# ADS1299IPAG.net
KiCad netlist of a schematic drawn in Altium Designer
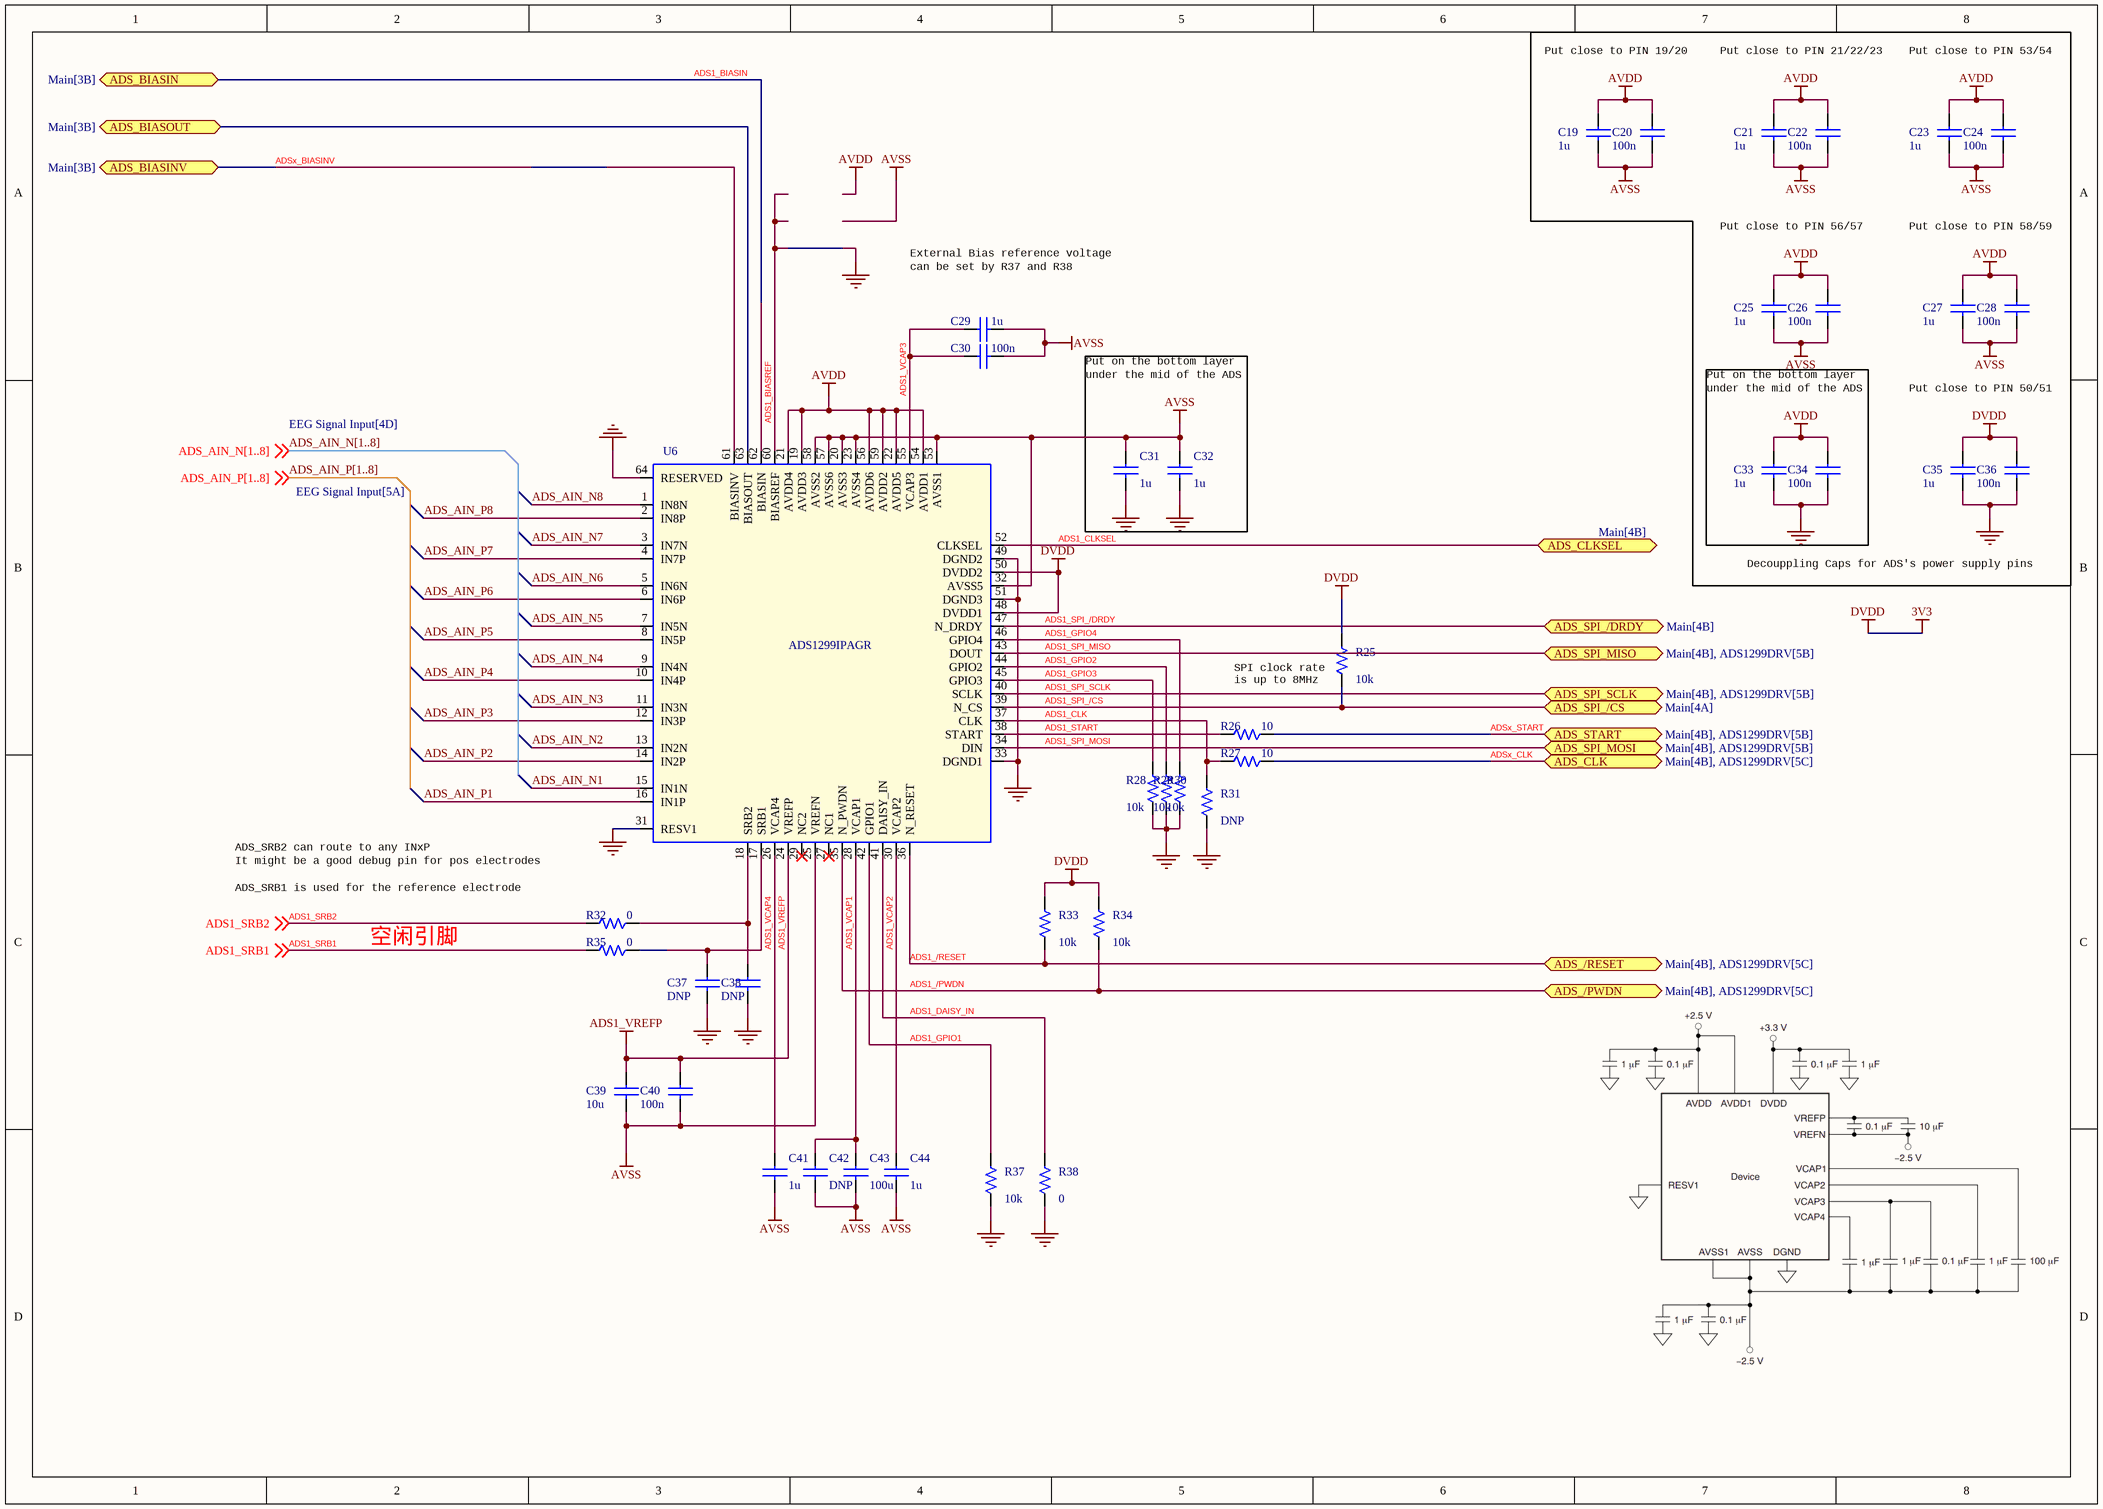
[diagram p0: ADS1299IPAG.SchDoc]

(export (version "E")
  (design (tool "Eeschema 10.0.6"))
  (components
    (comp (ref "C19")
      (value "1u")
      (footprint "0201_C")
      (description "CAP CER 1UF 25V X5R 0402")
      (fields
        (field (name "DISTRIBUTOR PART NUMBER") "C326568")
        (field (name "PART NUMBER") "CC0402KRX5R8BB105")
      )
      (libsource (lib "*") (part "CAP0402"))
    )
    (comp (ref "C20")
      (value "100n")
      (footprint "0201_C")
      (description "CAP CER 0.1UF 25V X7R 0402")
      (fields
        (field (name "DISTRIBUTOR PART NUMBER") "C105883")
        (field (name "PART NUMBER") "CC0402KRX7R8BB104")
      )
      (libsource (lib "*") (part "CAP0402"))
    )
    (comp (ref "C21")
      (value "1u")
      (footprint "0201_C")
      (description "CAP CER 1UF 25V X5R 0402")
      (fields
        (field (name "DISTRIBUTOR PART NUMBER") "C326568")
        (field (name "PART NUMBER") "CC0402KRX5R8BB105")
      )
      (libsource (lib "*") (part "CAP0402"))
    )
    (comp (ref "C22")
      (value "100n")
      (footprint "0201_C")
      (description "CAP CER 0.1UF 25V X7R 0402")
      (fields
        (field (name "DISTRIBUTOR PART NUMBER") "C105883")
        (field (name "PART NUMBER") "CC0402KRX7R8BB104")
      )
      (libsource (lib "*") (part "CAP0402"))
    )
    (comp (ref "C23")
      (value "1u")
      (footprint "0201_C")
      (description "CAP CER 1UF 25V X5R 0402")
      (fields
        (field (name "DISTRIBUTOR PART NUMBER") "C326568")
        (field (name "PART NUMBER") "CC0402KRX5R8BB105")
      )
      (libsource (lib "*") (part "CAP0402"))
    )
    (comp (ref "C24")
      (value "100n")
      (footprint "0201_C")
      (description "CAP CER 0.1UF 25V X7R 0402")
      (fields
        (field (name "DISTRIBUTOR PART NUMBER") "C105883")
        (field (name "PART NUMBER") "CC0402KRX7R8BB104")
      )
      (libsource (lib "*") (part "CAP0402"))
    )
    (comp (ref "C25")
      (value "1u")
      (footprint "0201_C")
      (description "CAP CER 1UF 25V X5R 0402")
      (fields
        (field (name "DISTRIBUTOR PART NUMBER") "C326568")
        (field (name "PART NUMBER") "CC0402KRX5R8BB105")
      )
      (libsource (lib "*") (part "CAP0402"))
    )
    (comp (ref "C26")
      (value "100n")
      (footprint "0201_C")
      (description "CAP CER 0.1UF 25V X7R 0402")
      (fields
        (field (name "DISTRIBUTOR PART NUMBER") "C105883")
        (field (name "PART NUMBER") "CC0402KRX7R8BB104")
      )
      (libsource (lib "*") (part "CAP0402"))
    )
    (comp (ref "C27")
      (value "1u")
      (footprint "0201_C")
      (description "CAP CER 1UF 25V X5R 0402")
      (fields
        (field (name "DISTRIBUTOR PART NUMBER") "C326568")
        (field (name "PART NUMBER") "CC0402KRX5R8BB105")
      )
      (libsource (lib "*") (part "CAP0402"))
    )
    (comp (ref "C28")
      (value "100n")
      (footprint "0201_C")
      (description "CAP CER 0.1UF 25V X7R 0402")
      (fields
        (field (name "DISTRIBUTOR PART NUMBER") "C105883")
        (field (name "PART NUMBER") "CC0402KRX7R8BB104")
      )
      (libsource (lib "*") (part "CAP0402"))
    )
    (comp (ref "C29")
      (value "1u")
      (footprint "0201_C")
      (description "CAP CER 1UF 25V X5R 0402")
      (fields
        (field (name "DISTRIBUTOR PART NUMBER") "C326568")
        (field (name "PART NUMBER") "CC0402KRX5R8BB105")
      )
      (libsource (lib "*") (part "CAP0402"))
    )
    (comp (ref "C30")
      (value "100n")
      (footprint "0201_C")
      (description "CAP CER 0.1UF 25V X7R 0402")
      (fields
        (field (name "DISTRIBUTOR PART NUMBER") "C105883")
        (field (name "PART NUMBER") "CC0402KRX7R8BB104")
      )
      (libsource (lib "*") (part "CAP0402"))
    )
    (comp (ref "C31")
      (value "1u")
      (footprint "0201_C")
      (description "CAP CER 1UF 25V X5R 0402")
      (fields
        (field (name "DISTRIBUTOR PART NUMBER") "C326568")
        (field (name "PART NUMBER") "CC0402KRX5R8BB105")
      )
      (libsource (lib "*") (part "CAP0402"))
    )
    (comp (ref "C32")
      (value "1u")
      (footprint "0201_C")
      (description "CAP CER 1UF 25V X5R 0402")
      (fields
        (field (name "DISTRIBUTOR PART NUMBER") "C326568")
        (field (name "PART NUMBER") "CC0402KRX5R8BB105")
      )
      (libsource (lib "*") (part "CAP0402"))
    )
    (comp (ref "C33")
      (value "1u")
      (footprint "0201_C")
      (description "CAP CER 1UF 25V X5R 0402")
      (fields
        (field (name "DISTRIBUTOR PART NUMBER") "C326568")
        (field (name "PART NUMBER") "CC0402KRX5R8BB105")
      )
      (libsource (lib "*") (part "CAP0402"))
    )
    (comp (ref "C34")
      (value "100n")
      (footprint "0201_C")
      (description "CAP CER 0.1UF 25V X7R 0402")
      (fields
        (field (name "DISTRIBUTOR PART NUMBER") "C105883")
        (field (name "PART NUMBER") "CC0402KRX7R8BB104")
      )
      (libsource (lib "*") (part "CAP0402"))
    )
    (comp (ref "C35")
      (value "1u")
      (footprint "0201_C")
      (description "CAP CER 1UF 25V X5R 0402")
      (fields
        (field (name "DISTRIBUTOR PART NUMBER") "C326568")
        (field (name "PART NUMBER") "CC0402KRX5R8BB105")
      )
      (libsource (lib "*") (part "CAP0402"))
    )
    (comp (ref "C36")
      (value "100n")
      (footprint "0201_C")
      (description "CAP CER 0.1UF 25V X7R 0402")
      (fields
        (field (name "DISTRIBUTOR PART NUMBER") "C105883")
        (field (name "PART NUMBER") "CC0402KRX7R8BB104")
      )
      (libsource (lib "*") (part "CAP0402"))
    )
    (comp (ref "C37") (value "DNP") (footprint "0402_C") (libsource (lib "*") (part "CAP0402")))
    (comp (ref "C38") (value "DNP") (footprint "0402_C") (libsource (lib "*") (part "CAP0402")))
    (comp (ref "C39")
      (value "10u")
      (footprint "0402_C")
      (description "CAP CER 10UF 10V X5R 0603")
      (fields
        (field (name "DISTRIBUTOR PART NUMBER") "C19702")
        (field (name "PART NUMBER") "CL10A106KP8NNNC")
      )
      (libsource (lib "*") (part "CAP0402"))
    )
    (comp (ref "C40")
      (value "100n")
      (footprint "0201_C")
      (description "CAP CER 0.1UF 25V X7R 0402")
      (fields
        (field (name "DISTRIBUTOR PART NUMBER") "C105883")
        (field (name "PART NUMBER") "CC0402KRX7R8BB104")
      )
      (libsource (lib "*") (part "CAP0402"))
    )
    (comp (ref "C41")
      (value "1u")
      (footprint "0201_C")
      (description "CAP CER 1UF 25V X5R 0402")
      (fields
        (field (name "DISTRIBUTOR PART NUMBER") "C326568")
        (field (name "PART NUMBER") "CC0402KRX5R8BB105")
      )
      (libsource (lib "*") (part "CAP0402"))
    )
    (comp (ref "C42") (value "DNP") (footprint "0201_C") (libsource (lib "*") (part "CAP0402")))
    (comp (ref "C43")
      (value "100u")
      (footprint "0201_C")
      (description "CAP CER 100UF 10V X5R 1206")
      (fields
        (field (name "DISTRIBUTOR PART NUMBER") "C312983")
        (field (name "PART NUMBER") "GRM31CR61A107ME05L")
      )
      (libsource (lib "*") (part "CAP0402"))
    )
    (comp (ref "C44")
      (value "1u")
      (footprint "0201_C")
      (description "CAP CER 1UF 25V X5R 0402")
      (fields
        (field (name "DISTRIBUTOR PART NUMBER") "C326568")
        (field (name "PART NUMBER") "CC0402KRX5R8BB105")
      )
      (libsource (lib "*") (part "CAP0402"))
    )
    (comp (ref "R25")
      (value "10k")
      (footprint "0201_R")
      (description "RES SMD 10K OHM 1% 1/16W 0402")
      (fields
        (field (name "MANUFACTURER") "YAGEO")
        (field (name "MANUFACTURER PART NUMBER") "RC0402FR-0710KL")
      )
      (libsource (lib "*") (part "RES"))
    )
    (comp (ref "R26")
      (value "10")
      (footprint "0201_R")
      (description "RES SMD 10 OHM 1% 1/10W 0402")
      (fields
        (field (name "MANUFACTURER") "YAGEO")
        (field (name "MANUFACTURER PART NUMBER") "RC0402FR-0710RL")
      )
      (libsource (lib "*") (part "RES"))
    )
    (comp (ref "R27")
      (value "10")
      (footprint "0201_R")
      (description "RES SMD 10 OHM 1% 1/10W 0402")
      (fields
        (field (name "MANUFACTURER") "YAGEO")
        (field (name "MANUFACTURER PART NUMBER") "RC0402FR-0710RL")
      )
      (libsource (lib "*") (part "RES"))
    )
    (comp (ref "R28")
      (value "10k")
      (footprint "0201_R")
      (description "RES SMD 10K OHM 1% 1/16W 0402")
      (fields
        (field (name "MANUFACTURER") "YAGEO")
        (field (name "MANUFACTURER PART NUMBER") "RC0402FR-0710KL")
      )
      (libsource (lib "*") (part "RES"))
    )
    (comp (ref "R29")
      (value "10k")
      (footprint "0201_R")
      (description "RES SMD 10K OHM 1% 1/16W 0402")
      (fields
        (field (name "MANUFACTURER") "YAGEO")
        (field (name "MANUFACTURER PART NUMBER") "RC0402FR-0710KL")
      )
      (libsource (lib "*") (part "RES"))
    )
    (comp (ref "R30")
      (value "10k")
      (footprint "0201_R")
      (description "RES SMD 10K OHM 1% 1/16W 0402")
      (fields
        (field (name "MANUFACTURER") "YAGEO")
        (field (name "MANUFACTURER PART NUMBER") "RC0402FR-0710KL")
      )
      (libsource (lib "*") (part "RES"))
    )
    (comp (ref "R31") (value "DNP") (footprint "0201_R") (libsource (lib "*") (part "RES")))
    (comp (ref "R32")
      (value "0")
      (footprint "0402_R")
      (description "RES SMD 0 OHM JUMPER 1/16W 0402")
      (fields
        (field (name "DISTRIBUTOR PART NUMBER") "C106231")
        (field (name "PART NUMBER") "RC0402FR-070RL")
      )
      (libsource (lib "*") (part "RES"))
    )
    (comp (ref "R33")
      (value "10k")
      (footprint "0201_R")
      (description "RES SMD 10K OHM 1% 1/16W 0402")
      (fields
        (field (name "DISTRIBUTOR PART NUMBER") "C60490")
        (field (name "PART NUMBER") "RC0402FR-0710KL")
      )
      (libsource (lib "*") (part "RES"))
    )
    (comp (ref "R34")
      (value "10k")
      (footprint "0201_R")
      (description "RES SMD 10K OHM 1% 1/16W 0402")
      (fields
        (field (name "DISTRIBUTOR PART NUMBER") "C60490")
        (field (name "PART NUMBER") "RC0402FR-0710KL")
      )
      (libsource (lib "*") (part "RES"))
    )
    (comp (ref "R35")
      (value "0")
      (footprint "0402_R")
      (description "RES SMD 0 OHM JUMPER 1/16W 0402")
      (fields
        (field (name "MANUFACTURER") "YAGEO")
        (field (name "MANUFACTURER PART NUMBER") "RC0402FR-070RL")
      )
      (libsource (lib "*") (part "RES"))
    )
    (comp (ref "R37")
      (value "10k")
      (footprint "0201_R")
      (description "RES SMD 10K OHM 1% 1/16W 0402")
      (fields
        (field (name "MANUFACTURER") "YAGEO")
        (field (name "MANUFACTURER PART NUMBER") "RC0402FR-0710KL")
      )
      (libsource (lib "*") (part "RES"))
    )
    (comp (ref "R38")
      (value "0")
      (footprint "0201_R")
      (description "RES SMD 0 OHM JUMPER 1/16W 0402")
      (fields
        (field (name "MANUFACTURER") "YAGEO")
        (field (name "MANUFACTURER PART NUMBER") "RC0402FR-070RL")
      )
      (libsource (lib "*") (part "RES"))
    )
    (comp (ref "U6")
      (value "ADS1299IPAGR")
      (footprint "TQFP-64_L10.0-W10.0-P0.50-LS12.0-TL")
      (description "IC AFE 8 CHAN 24BIT 64TQFP")
      (fields
        (field (name "MANUFACTURER") "Texas Instruments")
        (field (name "DISTRIBUTOR PART NUMBER") "296-34818-1-ND")
      )
      (libsource (lib "*") (part "ADS1299IPAGR"))
    )
  )
  (nets
    (net (code "1") (name "/ADS1_BIASIN") (class "Default")
      (node (ref "U6") (pin "62") (pinfunction "BIASIN_62") (pintype "passive"))
    )
    (net (code "2") (name "/ADS1_CLK") (class "Default")
      (node (ref "R27") (pin "2") (pinfunction "2_2") (pintype "passive"))
      (node (ref "R31") (pin "1") (pinfunction "1_1") (pintype "passive"))
      (node (ref "U6") (pin "37") (pinfunction "CLK_37") (pintype "passive"))
    )
    (net (code "3") (name "/ADS1_CLKSEL") (class "Default")
      (node (ref "U6") (pin "52") (pinfunction "CLKSEL_52") (pintype "passive"))
    )
    (net (code "4") (name "/ADS1_DAISY_IN") (class "Default")
      (node (ref "R38") (pin "1") (pinfunction "1_1") (pintype "passive"))
      (node (ref "U6") (pin "41") (pinfunction "DAISY_IN_41") (pintype "passive"))
    )
    (net (code "5") (name "/ADS1_GPIO1") (class "Default")
      (node (ref "R37") (pin "1") (pinfunction "1_1") (pintype "passive"))
      (node (ref "U6") (pin "42") (pinfunction "GPIO1_42") (pintype "passive"))
    )
    (net (code "6") (name "/ADS1_GPIO2") (class "Default")
      (node (ref "R29") (pin "1") (pinfunction "1_1") (pintype "passive"))
      (node (ref "U6") (pin "44") (pinfunction "GPIO2_44") (pintype "passive"))
    )
    (net (code "7") (name "/ADS1_GPIO3") (class "Default")
      (node (ref "R28") (pin "1") (pinfunction "1_1") (pintype "passive"))
      (node (ref "U6") (pin "45") (pinfunction "GPIO3_45") (pintype "passive"))
    )
    (net (code "8") (name "/ADS1_GPIO4") (class "Default")
      (node (ref "R30") (pin "1") (pinfunction "1_1") (pintype "passive"))
      (node (ref "U6") (pin "46") (pinfunction "GPIO4_46") (pintype "passive"))
    )
    (net (code "9") (name "/ADS1_SPI_MISO") (class "Default")
      (node (ref "U6") (pin "43") (pinfunction "DOUT_43") (pintype "passive"))
    )
    (net (code "10") (name "/ADS1_SPI_MOSI") (class "Default")
      (node (ref "U6") (pin "34") (pinfunction "DIN_34") (pintype "passive"))
    )
    (net (code "11") (name "/ADS1_SPI_SCLK") (class "Default")
      (node (ref "U6") (pin "40") (pinfunction "SCLK_40") (pintype "passive"))
    )
    (net (code "12") (name "/ADS1_SPI_{slash}CS") (class "Default")
      (node (ref "R25") (pin "2") (pinfunction "2_2") (pintype "passive"))
      (node (ref "U6") (pin "39") (pinfunction "N_CS_39") (pintype "passive"))
    )
    (net (code "13") (name "/ADS1_SPI_{slash}DRDY") (class "Default")
      (node (ref "U6") (pin "47") (pinfunction "N_DRDY_47") (pintype "passive"))
    )
    (net (code "14") (name "/ADS1_START") (class "Default")
      (node (ref "R26") (pin "2") (pinfunction "2_2") (pintype "passive"))
      (node (ref "U6") (pin "38") (pinfunction "START_38") (pintype "passive"))
    )
    (net (code "15") (name "/ADS1_VCAP1") (class "Default")
      (node (ref "C42") (pin "1") (pinfunction "1_1") (pintype "passive"))
      (node (ref "C43") (pin "1") (pinfunction "1_1") (pintype "passive"))
      (node (ref "U6") (pin "28") (pinfunction "VCAP1_28") (pintype "passive"))
    )
    (net (code "16") (name "/ADS1_VCAP2") (class "Default")
      (node (ref "C44") (pin "1") (pinfunction "1_1") (pintype "passive"))
      (node (ref "U6") (pin "30") (pinfunction "VCAP2_30") (pintype "passive"))
    )
    (net (code "17") (name "/ADS1_VCAP3") (class "Default")
      (node (ref "C29") (pin "1") (pinfunction "1_1") (pintype "passive"))
      (node (ref "C30") (pin "1") (pinfunction "1_1") (pintype "passive"))
      (node (ref "U6") (pin "55") (pinfunction "VCAP3_55") (pintype "passive"))
    )
    (net (code "18") (name "/ADS1_VCAP4") (class "Default")
      (node (ref "C41") (pin "1") (pinfunction "1_1") (pintype "passive"))
      (node (ref "U6") (pin "26") (pinfunction "VCAP4_26") (pintype "passive"))
    )
    (net (code "19") (name "/ADS1_{slash}PWDN") (class "Default")
      (node (ref "R34") (pin "2") (pinfunction "2_2") (pintype "passive"))
      (node (ref "U6") (pin "35") (pinfunction "N_PWDN_35") (pintype "passive"))
    )
    (net (code "20") (name "/ADS1_{slash}RESET") (class "Default")
      (node (ref "R33") (pin "2") (pinfunction "2_2") (pintype "passive"))
      (node (ref "U6") (pin "36") (pinfunction "N_RESET_36") (pintype "passive"))
    )
    (net (code "21") (name "/ADS_BIASOUT") (class "Default")
      (node (ref "U6") (pin "63") (pinfunction "BIASOUT_63") (pintype "passive"))
    )
    (net (code "22") (name "/ADSx_BIASINV") (class "Default")
      (node (ref "U6") (pin "61") (pinfunction "BIASINV_61") (pintype "passive"))
    )
    (net (code "23") (name "/ADSx_CLK") (class "Default")
      (node (ref "R27") (pin "1") (pinfunction "1_1") (pintype "passive"))
    )
    (net (code "24") (name "/ADSx_START") (class "Default")
      (node (ref "R26") (pin "1") (pinfunction "1_1") (pintype "passive"))
    )
    (net (code "25") (name "3V3") (class "Default")
      (node (ref "C35") (pin "1") (pinfunction "1_1") (pintype "passive"))
      (node (ref "C36") (pin "1") (pinfunction "1_1") (pintype "passive"))
      (node (ref "R25") (pin "1") (pinfunction "1_1") (pintype "passive"))
      (node (ref "R33") (pin "1") (pinfunction "1_1") (pintype "passive"))
      (node (ref "R34") (pin "1") (pinfunction "1_1") (pintype "passive"))
      (node (ref "U6") (pin "48") (pinfunction "DVDD1_48") (pintype "passive"))
      (node (ref "U6") (pin "50") (pinfunction "DVDD2_50") (pintype "passive"))
    )
    (net (code "26") (name "ADS1_SRB1") (class "Default")
      (node (ref "R35") (pin "2") (pinfunction "2_2") (pintype "passive"))
    )
    (net (code "27") (name "ADS1_SRB2") (class "Default")
      (node (ref "R32") (pin "2") (pinfunction "2_2") (pintype "passive"))
    )
    (net (code "28") (name "ADS1_VREFP") (class "Default")
      (node (ref "C39") (pin "1") (pinfunction "1_1") (pintype "passive"))
      (node (ref "C40") (pin "1") (pinfunction "1_1") (pintype "passive"))
      (node (ref "U6") (pin "24") (pinfunction "VREFP_24") (pintype "passive"))
    )
    (net (code "29") (name "ADS_AIN_N1") (class "Default")
      (node (ref "U6") (pin "15") (pinfunction "IN1N_15") (pintype "passive"))
    )
    (net (code "30") (name "ADS_AIN_N2") (class "Default")
      (node (ref "U6") (pin "13") (pinfunction "IN2N_13") (pintype "passive"))
    )
    (net (code "31") (name "ADS_AIN_N3") (class "Default")
      (node (ref "U6") (pin "11") (pinfunction "IN3N_11") (pintype "passive"))
    )
    (net (code "32") (name "ADS_AIN_N4") (class "Default")
      (node (ref "U6") (pin "9") (pinfunction "IN4N_9") (pintype "passive"))
    )
    (net (code "33") (name "ADS_AIN_N5") (class "Default")
      (node (ref "U6") (pin "7") (pinfunction "IN5N_7") (pintype "passive"))
    )
    (net (code "34") (name "ADS_AIN_N6") (class "Default")
      (node (ref "U6") (pin "5") (pinfunction "IN6N_5") (pintype "passive"))
    )
    (net (code "35") (name "ADS_AIN_N7") (class "Default")
      (node (ref "U6") (pin "3") (pinfunction "IN7N_3") (pintype "passive"))
    )
    (net (code "36") (name "ADS_AIN_N8") (class "Default")
      (node (ref "U6") (pin "1") (pinfunction "IN8N_1") (pintype "passive"))
    )
    (net (code "38") (name "ADS_AIN_P1") (class "Default")
      (node (ref "U6") (pin "16") (pinfunction "IN1P_16") (pintype "passive"))
    )
    (net (code "39") (name "ADS_AIN_P2") (class "Default")
      (node (ref "U6") (pin "14") (pinfunction "IN2P_14") (pintype "passive"))
    )
    (net (code "40") (name "ADS_AIN_P3") (class "Default")
      (node (ref "U6") (pin "12") (pinfunction "IN3P_12") (pintype "passive"))
    )
    (net (code "41") (name "ADS_AIN_P4") (class "Default")
      (node (ref "U6") (pin "10") (pinfunction "IN4P_10") (pintype "passive"))
    )
    (net (code "42") (name "ADS_AIN_P5") (class "Default")
      (node (ref "U6") (pin "8") (pinfunction "IN5P_8") (pintype "passive"))
    )
    (net (code "43") (name "ADS_AIN_P6") (class "Default")
      (node (ref "U6") (pin "6") (pinfunction "IN6P_6") (pintype "passive"))
    )
    (net (code "44") (name "ADS_AIN_P7") (class "Default")
      (node (ref "U6") (pin "4") (pinfunction "IN7P_4") (pintype "passive"))
    )
    (net (code "45") (name "ADS_AIN_P8") (class "Default")
      (node (ref "U6") (pin "2") (pinfunction "IN8P_2") (pintype "passive"))
    )
    (net (code "47") (name "AVDD") (class "Default")
      (node (ref "C19") (pin "1") (pinfunction "1_1") (pintype "passive"))
      (node (ref "C20") (pin "1") (pinfunction "1_1") (pintype "passive"))
      (node (ref "C21") (pin "1") (pinfunction "1_1") (pintype "passive"))
      (node (ref "C22") (pin "1") (pinfunction "1_1") (pintype "passive"))
      (node (ref "C23") (pin "1") (pinfunction "1_1") (pintype "passive"))
      (node (ref "C24") (pin "1") (pinfunction "1_1") (pintype "passive"))
      (node (ref "C25") (pin "1") (pinfunction "1_1") (pintype "passive"))
      (node (ref "C26") (pin "1") (pinfunction "1_1") (pintype "passive"))
      (node (ref "C27") (pin "1") (pinfunction "1_1") (pintype "passive"))
      (node (ref "C28") (pin "1") (pinfunction "1_1") (pintype "passive"))
      (node (ref "C33") (pin "1") (pinfunction "1_1") (pintype "passive"))
      (node (ref "C34") (pin "1") (pinfunction "1_1") (pintype "passive"))
      (node (ref "U6") (pin "19") (pinfunction "AVDD3_19") (pintype "passive"))
      (node (ref "U6") (pin "21") (pinfunction "AVDD4_21") (pintype "passive"))
      (node (ref "U6") (pin "22") (pinfunction "AVDD5_22") (pintype "passive"))
      (node (ref "U6") (pin "54") (pinfunction "AVDD1_54") (pintype "passive"))
      (node (ref "U6") (pin "56") (pinfunction "AVDD6_56") (pintype "passive"))
      (node (ref "U6") (pin "59") (pinfunction "AVDD2_59") (pintype "passive"))
    )
    (net (code "48") (name "AVSS") (class "Default")
      (node (ref "C19") (pin "2") (pinfunction "2_2") (pintype "passive"))
      (node (ref "C20") (pin "2") (pinfunction "2_2") (pintype "passive"))
      (node (ref "C21") (pin "2") (pinfunction "2_2") (pintype "passive"))
      (node (ref "C22") (pin "2") (pinfunction "2_2") (pintype "passive"))
      (node (ref "C23") (pin "2") (pinfunction "2_2") (pintype "passive"))
      (node (ref "C24") (pin "2") (pinfunction "2_2") (pintype "passive"))
      (node (ref "C25") (pin "2") (pinfunction "2_2") (pintype "passive"))
      (node (ref "C26") (pin "2") (pinfunction "2_2") (pintype "passive"))
      (node (ref "C27") (pin "2") (pinfunction "2_2") (pintype "passive"))
      (node (ref "C28") (pin "2") (pinfunction "2_2") (pintype "passive"))
      (node (ref "C29") (pin "2") (pinfunction "2_2") (pintype "passive"))
      (node (ref "C30") (pin "2") (pinfunction "2_2") (pintype "passive"))
      (node (ref "C31") (pin "1") (pinfunction "1_1") (pintype "passive"))
      (node (ref "C32") (pin "1") (pinfunction "1_1") (pintype "passive"))
      (node (ref "C39") (pin "2") (pinfunction "2_2") (pintype "passive"))
      (node (ref "C40") (pin "2") (pinfunction "2_2") (pintype "passive"))
      (node (ref "C41") (pin "2") (pinfunction "2_2") (pintype "passive"))
      (node (ref "C42") (pin "2") (pinfunction "2_2") (pintype "passive"))
      (node (ref "C43") (pin "2") (pinfunction "2_2") (pintype "passive"))
      (node (ref "C44") (pin "2") (pinfunction "2_2") (pintype "passive"))
      (node (ref "U6") (pin "20") (pinfunction "AVSS3_20") (pintype "passive"))
      (node (ref "U6") (pin "23") (pinfunction "AVSS4_23") (pintype "passive"))
      (node (ref "U6") (pin "25") (pinfunction "VREFN_25") (pintype "passive"))
      (node (ref "U6") (pin "32") (pinfunction "AVSS5_32") (pintype "passive"))
      (node (ref "U6") (pin "53") (pinfunction "AVSS1_53") (pintype "passive"))
      (node (ref "U6") (pin "57") (pinfunction "AVSS6_57") (pintype "passive"))
      (node (ref "U6") (pin "58") (pinfunction "AVSS2_58") (pintype "passive"))
    )
    (net (code "49") (name "GND") (class "Default")
      (node (ref "C31") (pin "2") (pinfunction "2_2") (pintype "passive"))
      (node (ref "C32") (pin "2") (pinfunction "2_2") (pintype "passive"))
      (node (ref "C33") (pin "2") (pinfunction "2_2") (pintype "passive"))
      (node (ref "C34") (pin "2") (pinfunction "2_2") (pintype "passive"))
      (node (ref "C35") (pin "2") (pinfunction "2_2") (pintype "passive"))
      (node (ref "C36") (pin "2") (pinfunction "2_2") (pintype "passive"))
      (node (ref "C37") (pin "2") (pinfunction "2_2") (pintype "passive"))
      (node (ref "C38") (pin "2") (pinfunction "2_2") (pintype "passive"))
      (node (ref "R28") (pin "2") (pinfunction "2_2") (pintype "passive"))
      (node (ref "R29") (pin "2") (pinfunction "2_2") (pintype "passive"))
      (node (ref "R30") (pin "2") (pinfunction "2_2") (pintype "passive"))
      (node (ref "R31") (pin "2") (pinfunction "2_2") (pintype "passive"))
      (node (ref "R37") (pin "2") (pinfunction "2_2") (pintype "passive"))
      (node (ref "R38") (pin "2") (pinfunction "2_2") (pintype "passive"))
      (node (ref "U6") (pin "31") (pinfunction "RESV1_31") (pintype "passive"))
      (node (ref "U6") (pin "33") (pinfunction "DGND1_33") (pintype "passive"))
      (node (ref "U6") (pin "49") (pinfunction "DGND2_49") (pintype "passive"))
      (node (ref "U6") (pin "51") (pinfunction "DGND3_51") (pintype "passive"))
      (node (ref "U6") (pin "60") (pinfunction "BIASREF_60") (pintype "passive"))
      (node (ref "U6") (pin "64") (pinfunction "RESERVED_64") (pintype "passive"))
    )
    (net (code "50") (name "Net-(U6-SRB1)") (class "Default")
      (node (ref "C37") (pin "1") (pinfunction "1_1") (pintype "passive"))
      (node (ref "R35") (pin "1") (pinfunction "1_1") (pintype "passive"))
      (node (ref "U6") (pin "17") (pinfunction "SRB1_17") (pintype "passive"))
    )
    (net (code "51") (name "Net-(U6-SRB2)") (class "Default")
      (node (ref "C38") (pin "1") (pinfunction "1_1") (pintype "passive"))
      (node (ref "R32") (pin "1") (pinfunction "1_1") (pintype "passive"))
      (node (ref "U6") (pin "18") (pinfunction "SRB2_18") (pintype "passive"))
    )
    (net (code "52") (name "unconnected-(U6-NC1-Pad27)") (class "Default")
      (node (ref "U6") (pin "27") (pinfunction "NC1_27") (pintype "passive+no_connect"))
    )
    (net (code "53") (name "unconnected-(U6-NC2-Pad29)") (class "Default")
      (node (ref "U6") (pin "29") (pinfunction "NC2_29") (pintype "passive+no_connect"))
    )
  )
)
